# adm823_Breakout_Board.net
KiCad netlist of a schematic drawn in EAGLE
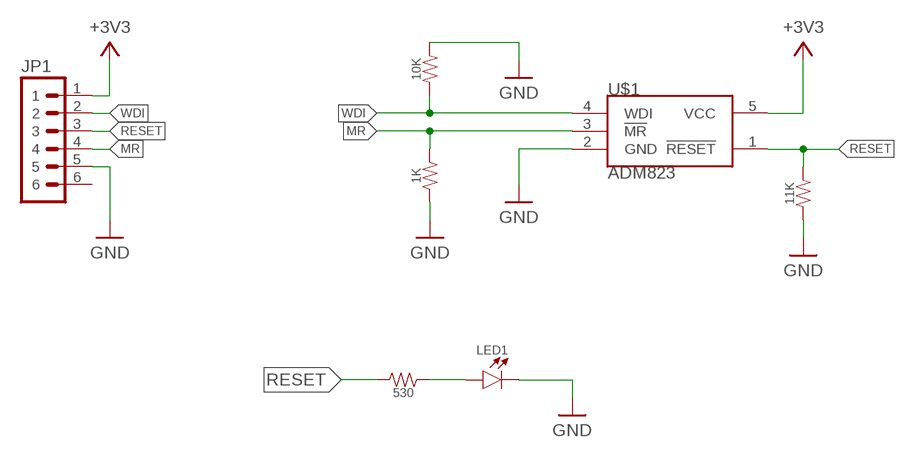
[diagram p0: schematic, sheet 1]

(export (version "E")
  (design (tool "Eeschema 10.0.6"))
  (components
    (comp (ref "1K")
      (value "RESISTOR_0603_")
      (footprint "eagle-import:0603-RES")
      (libsource (lib "eagle-import") (part "RESISTOR_?_0603"))
    )
    (comp (ref "10K")
      (value "10k")
      (footprint "eagle-import:0603-RES")
      (libsource (lib "eagle-import") (part "RESISTOR_?_0603"))
    )
    (comp (ref "11K")
      (value "10k")
      (footprint "eagle-import:0603-RES")
      (libsource (lib "eagle-import") (part "RESISTOR_?_0603"))
    )
    (comp (ref "530")
      (value "RESISTOR_0603_")
      (footprint "eagle-import:0603-RES")
      (libsource (lib "eagle-import") (part "RESISTOR_?_0603"))
    )
    (comp (ref "JP1")
      (value "M06")
      (footprint "eagle-import:1X06")
      (libsource (lib "eagle-import") (part "M06"))
    )
    (comp (ref "LED1")
      (value "LED-0603")
      (footprint "eagle-import:LED-603")
      (libsource (lib "eagle-import") (part "LED-0603"))
    )
    (comp (ref "U$1")
      (value "ADM823")
      (footprint "eagle-import:SOT323-5")
      (libsource (lib "eagle-import") (part "ADM823"))
    )
  )
  (nets
    (net (code "1") (name "+3V3") (class "Default")
      (node (ref "JP1") (pin "1") (pinfunction "1_1") (pintype "passive"))
      (node (ref "U$1") (pin "5") (pinfunction "VCC_5") (pintype "passive"))
    )
    (net (code "2") (name "GND") (class "Default")
      (node (ref "10K") (pin "2") (pinfunction "2_2") (pintype "passive"))
      (node (ref "11K") (pin "1") (pinfunction "1_1") (pintype "passive"))
      (node (ref "1K") (pin "1") (pinfunction "1_1") (pintype "passive"))
      (node (ref "JP1") (pin "5") (pinfunction "5_5") (pintype "passive"))
      (node (ref "LED1") (pin "C") (pinfunction "C_C") (pintype "passive"))
      (node (ref "U$1") (pin "2") (pinfunction "GND_2") (pintype "passive"))
    )
    (net (code "3") (name "MR") (class "Default")
      (node (ref "1K") (pin "2") (pinfunction "2_2") (pintype "passive"))
      (node (ref "JP1") (pin "4") (pinfunction "4_4") (pintype "passive"))
      (node (ref "U$1") (pin "3") (pinfunction "~{MR}_3") (pintype "passive"))
    )
    (net (code "4") (name "Net-(530-Pad1)") (class "Default")
      (node (ref "530") (pin "1") (pinfunction "1_1") (pintype "passive"))
      (node (ref "LED1") (pin "A") (pinfunction "A_A") (pintype "passive"))
    )
    (net (code "5") (name "RESET") (class "Default")
      (node (ref "11K") (pin "2") (pinfunction "2_2") (pintype "passive"))
      (node (ref "530") (pin "2") (pinfunction "2_2") (pintype "passive"))
      (node (ref "JP1") (pin "3") (pinfunction "3_3") (pintype "passive"))
      (node (ref "U$1") (pin "1") (pinfunction "~{RESET}_1") (pintype "passive"))
    )
    (net (code "6") (name "WDI") (class "Default")
      (node (ref "10K") (pin "1") (pinfunction "1_1") (pintype "passive"))
      (node (ref "JP1") (pin "2") (pinfunction "2_2") (pintype "passive"))
      (node (ref "U$1") (pin "4") (pinfunction "WDI_4") (pintype "passive"))
    )
    (net (code "7") (name "unconnected-(JP1-Pad6)") (class "Default")
      (node (ref "JP1") (pin "6") (pinfunction "6_6") (pintype "passive"))
    )
  )
)
